# UHF_Transceiver_Schematic.net
KiCad netlist of a schematic drawn in Altium Designer
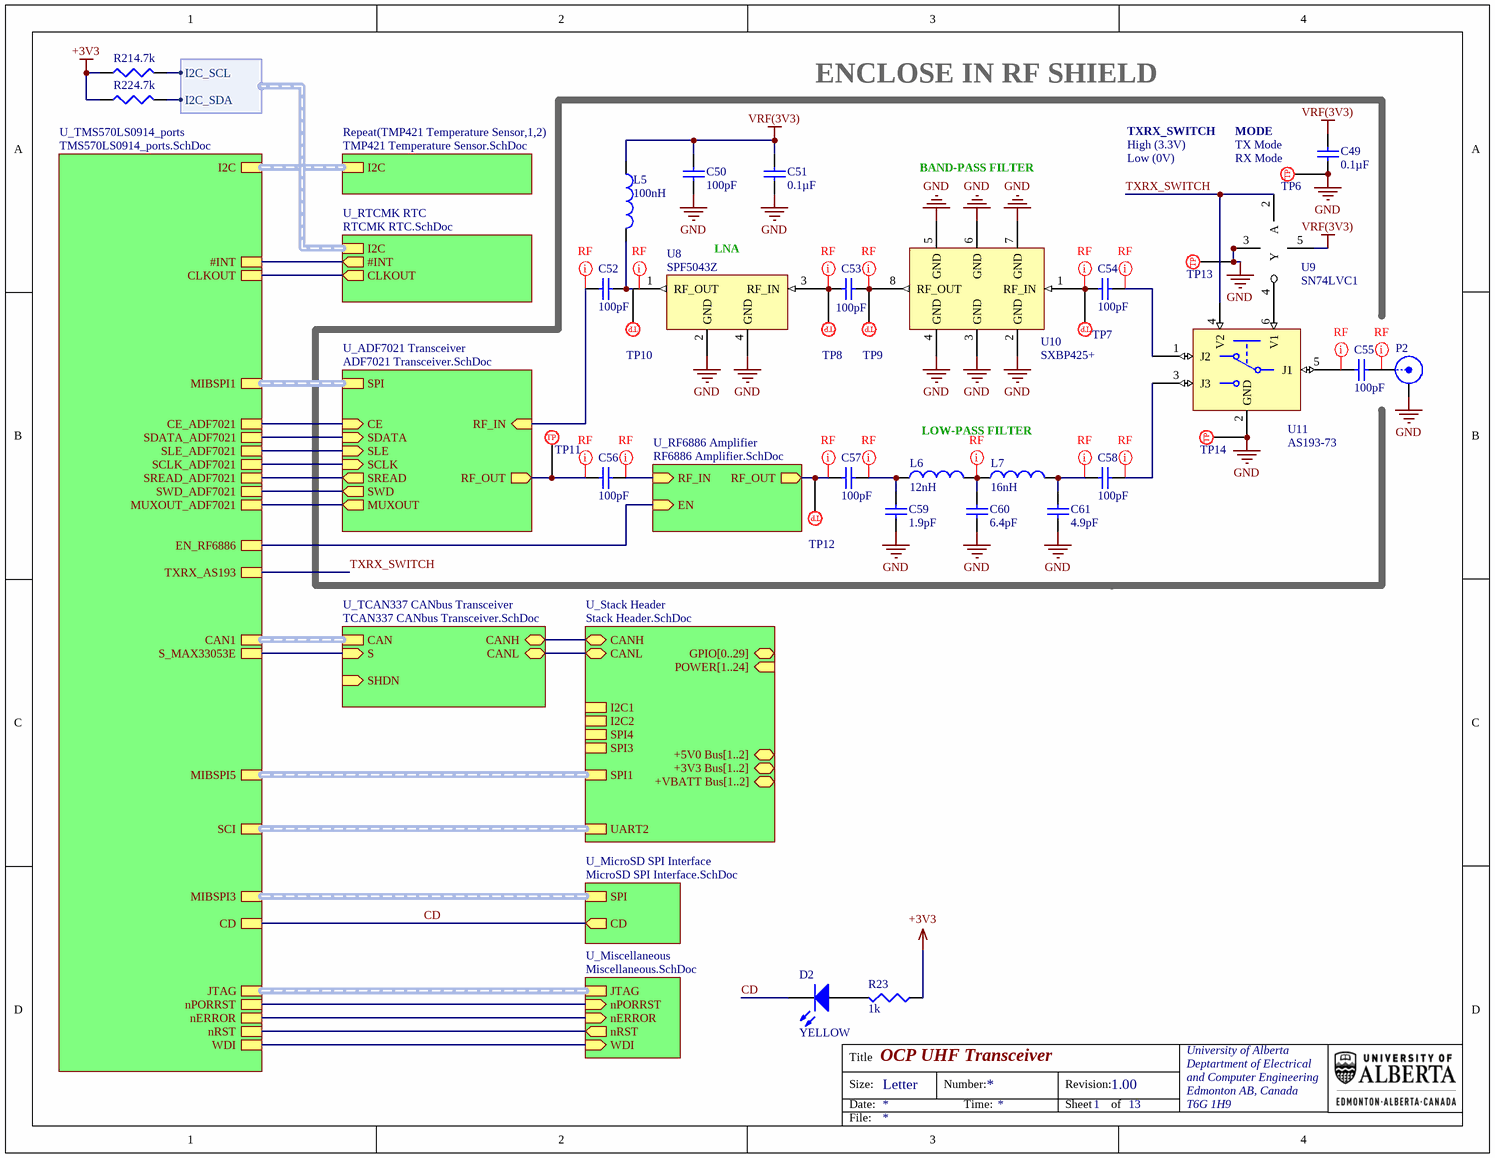
[diagram p0: UHF Transceiver Schematic.SchDoc]

(export (version "E")
  (design (tool "Eeschema 10.0.6"))
  (components
    (comp (ref "C49")
      (value "0.1µF")
      (footprint "TDK-CGA2B")
      (description "CAP CER 0.1UF 50V X7R 0402")
      (fields
        (field (name "PART NUMBER") "PC-TDK-02259")
        (field (name "MANUFACTURER PART NUMBER") "CGA2B3X7R1H104K050BB")
        (field (name "PUBLISHER") "AlbertaSat")
      )
      (libsource (lib "Database") (part "Cap"))
    )
    (comp (ref "C50")
      (value "100pF")
      (footprint "KEM-CBR04")
      (description "CAP CER SMD CBR 0402 100PF 5% 25")
      (fields
        (field (name "PART NUMBER") "PC-KEM-03159")
        (field (name "MANUFACTURER PART NUMBER") "CBR04C101J3GAC")
        (field (name "PUBLISHER") "AlbertaSat")
      )
      (libsource (lib "Database") (part "Cap"))
    )
    (comp (ref "C51")
      (value "0.1µF")
      (footprint "TDK-CGA2B")
      (description "CAP CER 0.1UF 50V X7R 0402")
      (fields
        (field (name "PART NUMBER") "PC-TDK-02259")
        (field (name "MANUFACTURER PART NUMBER") "CGA2B3X7R1H104K050BB")
        (field (name "PUBLISHER") "AlbertaSat")
      )
      (libsource (lib "Database") (part "Cap"))
    )
    (comp (ref "C52")
      (value "100pF")
      (footprint "KEM-CBR04")
      (description "CAP CER SMD CBR 0402 100PF 5% 25")
      (fields
        (field (name "PART NUMBER") "PC-KEM-03159")
        (field (name "MANUFACTURER PART NUMBER") "CBR04C101J3GAC")
        (field (name "PUBLISHER") "AlbertaSat")
      )
      (libsource (lib "Database") (part "Cap"))
    )
    (comp (ref "C53")
      (value "100pF")
      (footprint "KEM-CBR04")
      (description "CAP CER SMD CBR 0402 100PF 5% 25")
      (fields
        (field (name "PART NUMBER") "PC-KEM-03159")
        (field (name "MANUFACTURER PART NUMBER") "CBR04C101J3GAC")
        (field (name "PUBLISHER") "AlbertaSat")
      )
      (libsource (lib "Database") (part "Cap"))
    )
    (comp (ref "C54")
      (value "100pF")
      (footprint "KEM-CBR04")
      (description "CAP CER SMD CBR 0402 100PF 5% 25")
      (fields
        (field (name "PART NUMBER") "PC-KEM-03159")
        (field (name "MANUFACTURER PART NUMBER") "CBR04C101J3GAC")
        (field (name "PUBLISHER") "AlbertaSat")
      )
      (libsource (lib "Database") (part "Cap"))
    )
    (comp (ref "C55")
      (value "100pF")
      (footprint "KEM-CBR04")
      (description "CAP CER SMD CBR 0402 100PF 5% 25")
      (fields
        (field (name "PART NUMBER") "PC-KEM-03159")
        (field (name "MANUFACTURER PART NUMBER") "CBR04C101J3GAC")
        (field (name "PUBLISHER") "AlbertaSat")
      )
      (libsource (lib "Database") (part "Cap"))
    )
    (comp (ref "C56")
      (value "100pF")
      (footprint "KEM-CBR04")
      (description "CAP CER SMD CBR 0402 100PF 5% 25")
      (fields
        (field (name "PART NUMBER") "PC-KEM-03159")
        (field (name "MANUFACTURER PART NUMBER") "CBR04C101J3GAC")
        (field (name "PUBLISHER") "AlbertaSat")
      )
      (libsource (lib "Database") (part "Cap"))
    )
    (comp (ref "C57")
      (value "100pF")
      (footprint "KEM-CBR04")
      (description "CAP CER SMD CBR 0402 100PF 5% 25")
      (fields
        (field (name "PART NUMBER") "PC-KEM-03159")
        (field (name "MANUFACTURER PART NUMBER") "CBR04C101J3GAC")
        (field (name "PUBLISHER") "AlbertaSat")
      )
      (libsource (lib "Database") (part "Cap"))
    )
    (comp (ref "C58")
      (value "100pF")
      (footprint "KEM-CBR04")
      (description "CAP CER SMD CBR 0402 100PF 5% 25")
      (fields
        (field (name "PART NUMBER") "PC-KEM-03159")
        (field (name "MANUFACTURER PART NUMBER") "CBR04C101J3GAC")
        (field (name "PUBLISHER") "AlbertaSat")
      )
      (libsource (lib "Database") (part "Cap"))
    )
    (comp (ref "C59")
      (value "1.9pF")
      (footprint "KEM-CBR04")
      (description "CAP CER RF 1.9PF 50V +/-0.1 PF C")
      (fields
        (field (name "PART NUMBER") "PC-KEM-02905")
        (field (name "MANUFACTURER PART NUMBER") "CBR04C199B5GAC")
        (field (name "PUBLISHER") "AlbertaSat")
      )
      (libsource (lib "Database") (part "Cap"))
    )
    (comp (ref "C60")
      (value "6.4pF")
      (footprint "KEM-CBR04")
      (description "CAP CER RF 6.4PF 50V +/-0.1 PF C")
      (fields
        (field (name "PART NUMBER") "PC-KEM-03022")
        (field (name "MANUFACTURER PART NUMBER") "CBR04C649B5GAC")
        (field (name "PUBLISHER") "AlbertaSat")
      )
      (libsource (lib "Database") (part "Cap"))
    )
    (comp (ref "C61")
      (value "4.9pF")
      (footprint "KEM-CBR04")
      (description "CAP CER RF 4.9PF 50V +/-0.1 PF C")
      (fields
        (field (name "PART NUMBER") "PC-KEM-02983")
        (field (name "MANUFACTURER PART NUMBER") "CBR04C499B5GAC")
        (field (name "PUBLISHER") "AlbertaSat")
      )
      (libsource (lib "Database") (part "Cap"))
    )
    (comp (ref "D2")
      (value "YELLOW")
      (footprint "WL-150060XS75000")
      (description "LED YELLOW CLEAR 0603 SMD")
      (fields
        (field (name "PART NUMBER") "5")
        (field (name "MANUFACTURER PART NUMBER") "150060YS75000")
        (field (name "PUBLISHER") "Altium Limited")
      )
      (libsource (lib "Database") (part "LED0"))
    )
    (comp (ref "L5")
      (value "100nH")
      (footprint "TDK-MLF1005")
      (description "FIXD IND 100NH 180MA 510MOHM SMD")
      (fields
        (field (name "PART NUMBER") "PL-TDK-02957")
        (field (name "MANUFACTURER PART NUMBER") "MLF1005VR10JTD25")
        (field (name "PUBLISHER") "AlbertaSat")
      )
      (libsource (lib "Database") (part "Inductor"))
    )
    (comp (ref "L6")
      (value "12nH")
      (footprint "MUR-LQW15A")
      (description "FIXED IND 12NH 1.24A 93 MOHM")
      (fields
        (field (name "PART NUMBER") "10160")
        (field (name "MANUFACTURER PART NUMBER") "LQW15AN12NG8ZD")
        (field (name "PUBLISHER") "Altium Limited")
      )
      (libsource (lib "Database") (part "Inductor"))
    )
    (comp (ref "L7")
      (value "16nH")
      (footprint "MUR-LQW15A")
      (description "FIXED IND 16NH 1A 126 MOHM")
      (fields
        (field (name "PART NUMBER") "10161")
        (field (name "MANUFACTURER PART NUMBER") "LQW15AN16NG8ZD")
        (field (name "PUBLISHER") "Altium Limited")
      )
      (libsource (lib "Database") (part "Inductor"))
    )
    (comp (ref "P2")
      (value "903-518J-51P")
      (footprint "AMP-903-518J-51P")
      (description "CONN SMB JACK STR 50OHM EDGE MNT")
      (fields (field (name "PART NUMBER") "PP-AMP-00002") (field (name "PUBLISHER") "AlbertaSat"))
      (libsource (lib "Database") (part "SMB"))
    )
    (comp (ref "R21")
      (value "4.7k")
      (footprint "PANA-ERJ2R")
      (description "RES SMD 4.7K OHM 1% 1/10W 0402")
      (fields
        (field (name "PART NUMBER") "16657")
        (field (name "MANUFACTURER PART NUMBER") "ERJ-2RKF4701X")
        (field (name "PUBLISHER") "Altium Limited")
      )
      (libsource (lib "Database") (part "Res3"))
    )
    (comp (ref "R22")
      (value "4.7k")
      (footprint "PANA-ERJ2R")
      (description "RES SMD 4.7K OHM 1% 1/10W 0402")
      (fields
        (field (name "PART NUMBER") "16657")
        (field (name "MANUFACTURER PART NUMBER") "ERJ-2RKF4701X")
        (field (name "PUBLISHER") "Altium Limited")
      )
      (libsource (lib "Database") (part "Res3"))
    )
    (comp (ref "R23")
      (value "1k")
      (footprint "PANA-ERJ3EK")
      (description "RES SMD 1K OHM 1% 1/10W 0603")
      (fields
        (field (name "PART NUMBER") "15398")
        (field (name "MANUFACTURER PART NUMBER") "ERJ-3EKF1001V")
        (field (name "PUBLISHER") "Altium Limited")
      )
      (libsource (lib "Database") (part "Res3"))
    )
    (comp (ref "TP6")
      (value "5017")
      (footprint "KS-5017")
      (description "PC TEST POINT MINI SMD")
      (fields (field (name "PART NUMBER") "PTP-KS-00001") (field (name "PUBLISHER") "AlbertaSat"))
      (libsource (lib "Database") (part "5017"))
    )
    (comp (ref "TP7")
      (value "5017")
      (footprint "KS-5017")
      (description "PC TEST POINT MINI SMD")
      (fields (field (name "PART NUMBER") "PTP-KS-00001") (field (name "PUBLISHER") "AlbertaSat"))
      (libsource (lib "Database") (part "5017"))
    )
    (comp (ref "TP8")
      (value "5017")
      (footprint "KS-5017")
      (description "PC TEST POINT MINI SMD")
      (fields (field (name "PART NUMBER") "PTP-KS-00001") (field (name "PUBLISHER") "AlbertaSat"))
      (libsource (lib "Database") (part "5017"))
    )
    (comp (ref "TP9")
      (value "5017")
      (footprint "KS-5017")
      (description "PC TEST POINT MINI SMD")
      (fields (field (name "PART NUMBER") "PTP-KS-00001") (field (name "PUBLISHER") "AlbertaSat"))
      (libsource (lib "Database") (part "5017"))
    )
    (comp (ref "TP10")
      (value "5017")
      (footprint "KS-5017")
      (description "PC TEST POINT MINI SMD")
      (fields (field (name "PART NUMBER") "PTP-KS-00001") (field (name "PUBLISHER") "AlbertaSat"))
      (libsource (lib "Database") (part "5017"))
    )
    (comp (ref "TP11")
      (value "5017")
      (footprint "KS-5017")
      (description "PC TEST POINT MINI SMD")
      (fields (field (name "PART NUMBER") "PTP-KS-00001") (field (name "PUBLISHER") "AlbertaSat"))
      (libsource (lib "Database") (part "5017"))
    )
    (comp (ref "TP12")
      (value "5017")
      (footprint "KS-5017")
      (description "PC TEST POINT MINI SMD")
      (fields (field (name "PART NUMBER") "PTP-KS-00001") (field (name "PUBLISHER") "AlbertaSat"))
      (libsource (lib "Database") (part "5017"))
    )
    (comp (ref "TP13")
      (value "5017")
      (footprint "KS-5017")
      (description "PC TEST POINT MINI SMD")
      (fields (field (name "PART NUMBER") "PTP-KS-00001") (field (name "PUBLISHER") "AlbertaSat"))
      (libsource (lib "Database") (part "5017"))
    )
    (comp (ref "TP14")
      (value "5017")
      (footprint "KS-5017")
      (description "PC TEST POINT MINI SMD")
      (fields (field (name "PART NUMBER") "PTP-KS-00001") (field (name "PUBLISHER") "AlbertaSat"))
      (libsource (lib "Database") (part "5017"))
    )
    (comp (ref "U8")
      (value "SPF5043Z")
      (footprint "QRV-SOT-343-4")
      (description "RF Amplifier .05-4GHz SSG 12.9dB NF .8dB GaAs")
      (fields (field (name "PART NUMBER") "PU-QRV-00002") (field (name "PUBLISHER") "AlbertaSat"))
      (libsource (lib "Database") (part "SPF5043Z"))
    )
    (comp (ref "U9")
      (value "SN74LVC1")
      (footprint "TI-DBV0005A")
      (description "IC INVERTER SCHMITT 1CH SOT23-5")
      (fields
        (field (name "PART NUMBER") "52")
        (field (name "MANUFACTURER PART NUMBER") "SN74LVC1G14MDBVREP")
      )
      (libsource (lib "Database") (part "SN74LVC1G14MDBV"))
    )
    (comp (ref "U10")
      (value "SXBP425+")
      (footprint "MICI-SXBP")
      (description "Band Pass Filter")
      (fields
        (field (name "PART NUMBER") "PU-MICI-00002")
        (field (name "MANUFACTURER PART NUMBER") "SXBP-425+")
        (field (name "PUBLISHER") "AlbertaSat")
      )
      (libsource (lib "Database") (part "SXBP-425+"))
    )
    (comp (ref "U11")
      (value "AS193-73")
      (footprint "SKYW-SOT-6")
      (description "IC SW SPDT 0.1-2.5GHZ SOT6")
      (fields
        (field (name "PART NUMBER") "PU-SKYW-00003")
        (field (name "MANUFACTURER PART NUMBER") "AS193-73LF")
        (field (name "PUBLISHER") "AlbertaSat")
      )
      (libsource (lib "Database") (part "AS193-73"))
    )
  )
  (nets
    (net (code "2") (name "+3V3") (class "Default")
      (node (ref "R21") (pin "1") (pinfunction "1_1") (pintype "passive"))
      (node (ref "R22") (pin "1") (pinfunction "1_1") (pintype "passive"))
      (node (ref "R23") (pin "1") (pinfunction "1_1") (pintype "passive"))
    )
    (net (code "10") (name "/CD") (class "Default")
      (node (ref "D2") (pin "2") (pinfunction "K_2") (pintype "passive"))
    )
    (net (code "23") (name "/RF_IN") (class "Default")
      (node (ref "C52") (pin "2") (pinfunction "2_2") (pintype "passive"))
    )
    (net (code "24") (name "/RF_IN_1") (class "Default")
      (node (ref "C56") (pin "1") (pinfunction "1_1") (pintype "passive"))
    )
    (net (code "25") (name "/RF_OUT") (class "Default")
      (node (ref "C57") (pin "2") (pinfunction "2_2") (pintype "passive"))
      (node (ref "TP12") (pin "1") (pinfunction "1_1") (pintype "passive"))
    )
    (net (code "26") (name "/RF_OUT_1") (class "Default")
      (node (ref "C56") (pin "2") (pinfunction "2_2") (pintype "passive"))
      (node (ref "TP11") (pin "1") (pinfunction "1_1") (pintype "passive"))
    )
    (net (code "37") (name "/TXRX_SWITCH") (class "Default")
      (node (ref "U11") (pin "4") (pinfunction "V2_4") (pintype "input"))
      (node (ref "U9") (pin "2") (pinfunction "A_2") (pintype "passive"))
    )
    (net (code "43") (name "GND") (class "Default")
      (node (ref "C49") (pin "2") (pinfunction "2_2") (pintype "passive"))
      (node (ref "C50") (pin "1") (pinfunction "1_1") (pintype "passive"))
      (node (ref "C51") (pin "2") (pinfunction "2_2") (pintype "passive"))
      (node (ref "C59") (pin "1") (pinfunction "1_1") (pintype "passive"))
      (node (ref "C60") (pin "1") (pinfunction "1_1") (pintype "passive"))
      (node (ref "C61") (pin "1") (pinfunction "1_1") (pintype "passive"))
      (node (ref "P2") (pin "2") (pinfunction "Y_2") (pintype "passive"))
      (node (ref "TP13") (pin "1") (pinfunction "1_1") (pintype "passive"))
      (node (ref "TP14") (pin "1") (pinfunction "1_1") (pintype "passive"))
      (node (ref "TP6") (pin "1") (pinfunction "1_1") (pintype "passive"))
      (node (ref "U10") (pin "2") (pinfunction "GND_2") (pintype "passive"))
      (node (ref "U10") (pin "3") (pinfunction "GND_3") (pintype "passive"))
      (node (ref "U10") (pin "4") (pinfunction "GND_4") (pintype "passive"))
      (node (ref "U10") (pin "5") (pinfunction "GND_5") (pintype "passive"))
      (node (ref "U10") (pin "6") (pinfunction "GND_6") (pintype "passive"))
      (node (ref "U10") (pin "7") (pinfunction "GND_7") (pintype "passive"))
      (node (ref "U11") (pin "2") (pinfunction "GND_2") (pintype "power_in"))
      (node (ref "U8") (pin "2") (pinfunction "GND_2") (pintype "power_in"))
      (node (ref "U8") (pin "4") (pinfunction "GND_4") (pintype "power_in"))
      (node (ref "U9") (pin "1") (pinfunction "NC_1") (pintype "passive"))
      (node (ref "U9") (pin "3") (pinfunction "GND_3") (pintype "passive"))
    )
    (net (code "44") (name "Net-(C57-Pad1)") (class "Default")
      (node (ref "C57") (pin "1") (pinfunction "1_1") (pintype "passive"))
      (node (ref "C59") (pin "2") (pinfunction "2_2") (pintype "passive"))
      (node (ref "L6") (pin "1") (pinfunction "1_1") (pintype "passive"))
    )
    (net (code "45") (name "Net-(C58-Pad2)") (class "Default")
      (node (ref "C58") (pin "2") (pinfunction "2_2") (pintype "passive"))
      (node (ref "C61") (pin "2") (pinfunction "2_2") (pintype "passive"))
      (node (ref "L7") (pin "2") (pinfunction "2_2") (pintype "passive"))
    )
    (net (code "46") (name "Net-(C60-Pad2)") (class "Default")
      (node (ref "C60") (pin "2") (pinfunction "2_2") (pintype "passive"))
      (node (ref "L6") (pin "2") (pinfunction "2_2") (pintype "passive"))
      (node (ref "L7") (pin "1") (pinfunction "1_1") (pintype "passive"))
    )
    (net (code "47") (name "Net-(D2-A)") (class "Default")
      (node (ref "D2") (pin "1") (pinfunction "A_1") (pintype "passive"))
      (node (ref "R23") (pin "2") (pinfunction "2_2") (pintype "passive"))
    )
    (net (code "48") (name "Net-(P2-X)") (class "Default")
      (node (ref "C55") (pin "1") (pinfunction "1_1") (pintype "passive"))
      (node (ref "P2") (pin "1") (pinfunction "X_1") (pintype "passive"))
    )
    (net (code "49") (name "Net-(U8-RF_IN)") (class "Default")
      (node (ref "C53") (pin "2") (pinfunction "2_2") (pintype "passive"))
      (node (ref "TP8") (pin "1") (pinfunction "1_1") (pintype "passive"))
      (node (ref "U8") (pin "3") (pinfunction "RF_IN_3") (pintype "input"))
    )
    (net (code "50") (name "Net-(U8-RF_OUT)") (class "Default")
      (node (ref "C52") (pin "1") (pinfunction "1_1") (pintype "passive"))
      (node (ref "L5") (pin "2") (pinfunction "2_2") (pintype "passive"))
      (node (ref "TP10") (pin "1") (pinfunction "1_1") (pintype "passive"))
      (node (ref "U8") (pin "1") (pinfunction "RF_OUT_1") (pintype "output"))
    )
    (net (code "51") (name "Net-(U10-RF_IN)") (class "Default")
      (node (ref "C54") (pin "2") (pinfunction "2_2") (pintype "passive"))
      (node (ref "TP7") (pin "1") (pinfunction "1_1") (pintype "passive"))
      (node (ref "U10") (pin "1") (pinfunction "RF_IN_1") (pintype "input"))
    )
    (net (code "52") (name "Net-(U10-RF_OUT)") (class "Default")
      (node (ref "C53") (pin "1") (pinfunction "1_1") (pintype "passive"))
      (node (ref "TP9") (pin "1") (pinfunction "1_1") (pintype "passive"))
      (node (ref "U10") (pin "8") (pinfunction "RF_OUT_8") (pintype "output"))
    )
    (net (code "53") (name "Net-(U11-J1)") (class "Default")
      (node (ref "C55") (pin "2") (pinfunction "2_2") (pintype "passive"))
      (node (ref "U11") (pin "5") (pinfunction "J1_5") (pintype "bidirectional"))
    )
    (net (code "54") (name "Net-(U11-J2)") (class "Default")
      (node (ref "C54") (pin "1") (pinfunction "1_1") (pintype "passive"))
      (node (ref "U11") (pin "1") (pinfunction "J2_1") (pintype "bidirectional"))
    )
    (net (code "55") (name "Net-(U11-J3)") (class "Default")
      (node (ref "C58") (pin "1") (pinfunction "1_1") (pintype "passive"))
      (node (ref "U11") (pin "3") (pinfunction "J3_3") (pintype "bidirectional"))
    )
    (net (code "56") (name "Net-(U11-V1)") (class "Default")
      (node (ref "U11") (pin "6") (pinfunction "V1_6") (pintype "input"))
      (node (ref "U9") (pin "4") (pinfunction "Y_4") (pintype "passive"))
    )
    (net (code "57") (name "VRF(3V3)") (class "Default")
      (node (ref "C49") (pin "1") (pinfunction "1_1") (pintype "passive"))
      (node (ref "C50") (pin "2") (pinfunction "2_2") (pintype "passive"))
      (node (ref "C51") (pin "1") (pinfunction "1_1") (pintype "passive"))
      (node (ref "L5") (pin "1") (pinfunction "1_1") (pintype "passive"))
      (node (ref "U9") (pin "5") (pinfunction "VCC_5") (pintype "passive"))
    )
    (net (code "58") (name "unconnected-(R21-Pad2)") (class "Default")
      (node (ref "R21") (pin "2") (pinfunction "2_2") (pintype "passive"))
    )
    (net (code "59") (name "unconnected-(R22-Pad2)") (class "Default")
      (node (ref "R22") (pin "2") (pinfunction "2_2") (pintype "passive"))
    )
  )
)
